# SparkFun_ESP8266_Thing.net
KiCad netlist of a schematic drawn in EAGLE
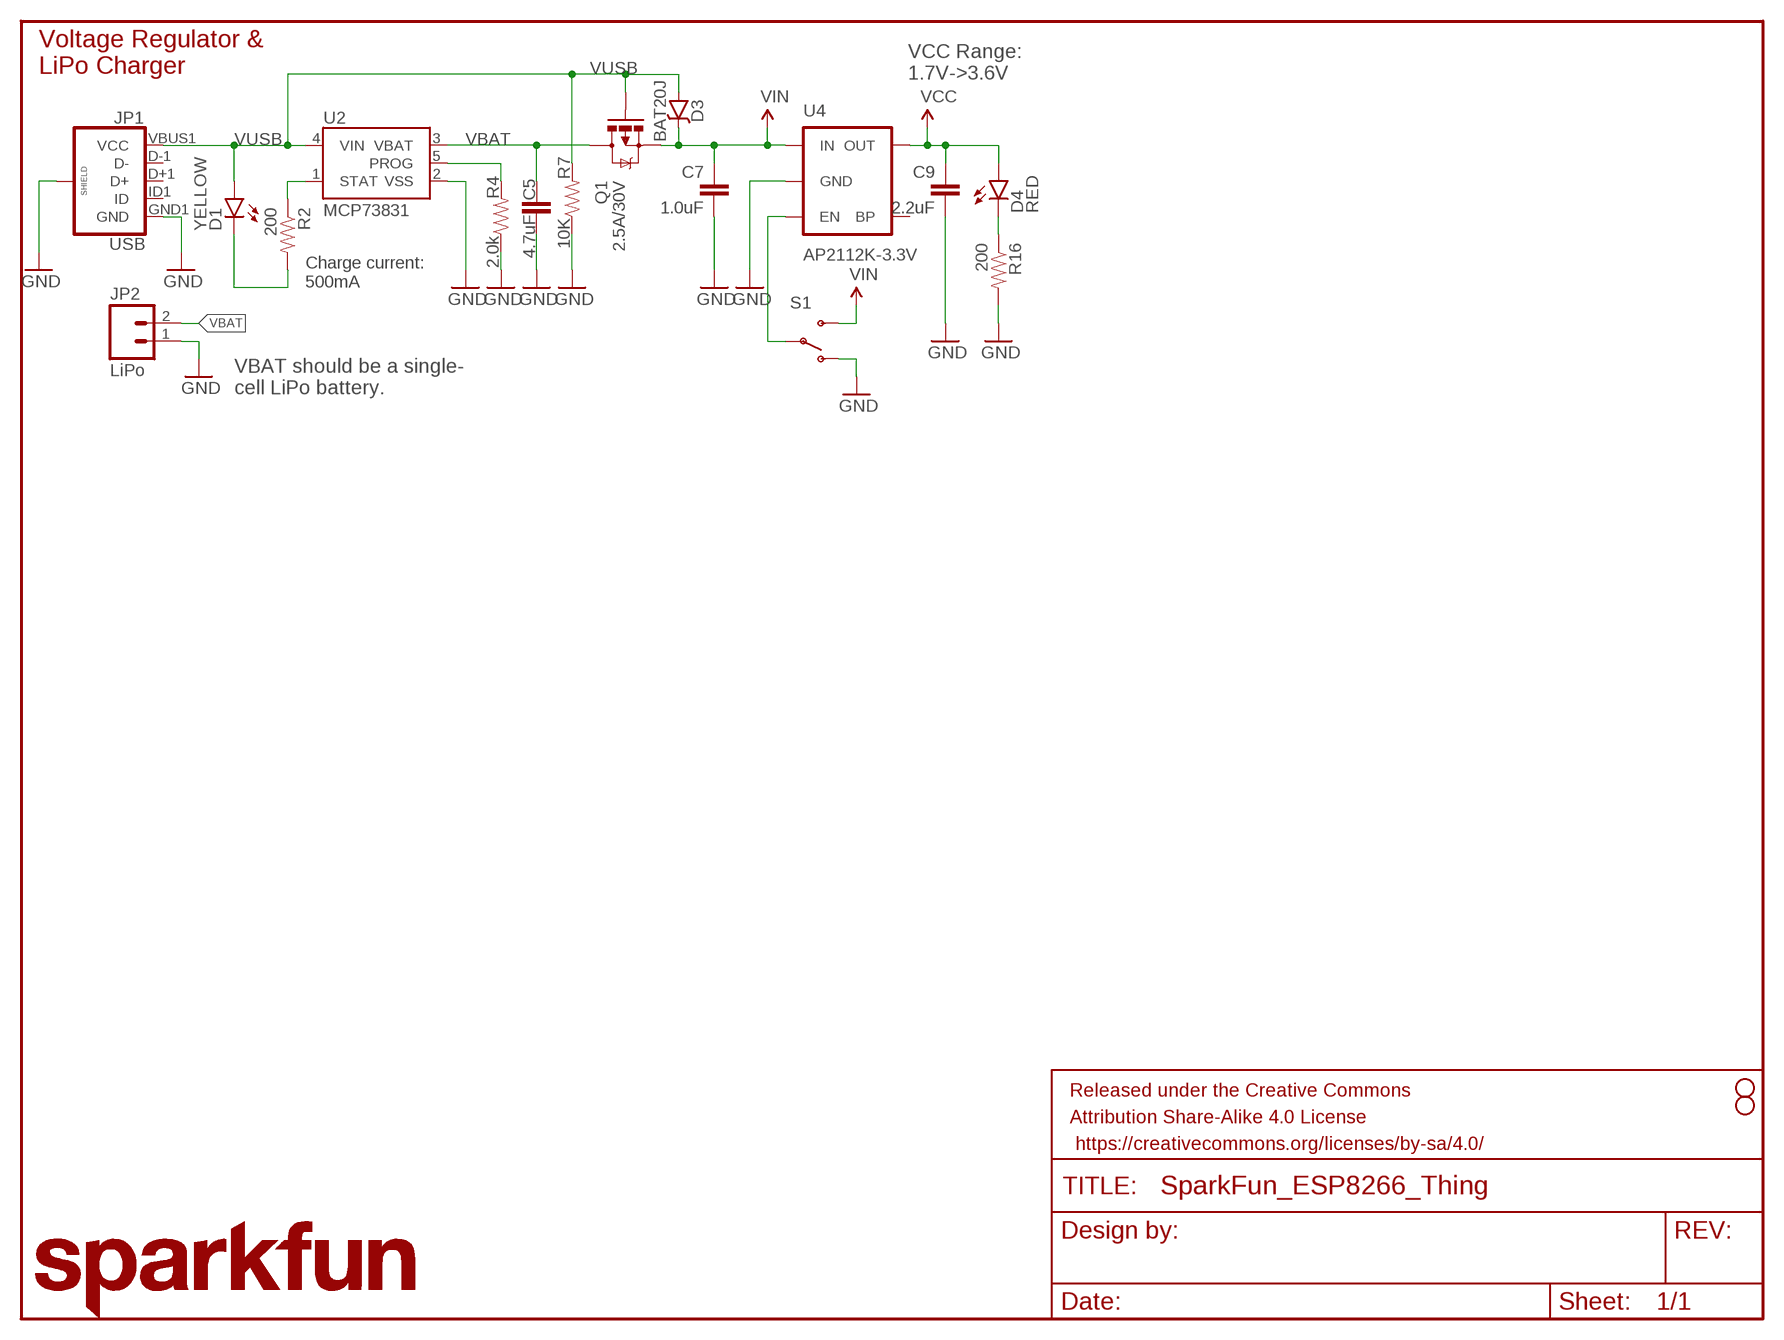
[diagram p0: schematic, sheet 1]

(export (version "E")
  (design (tool "Eeschema 10.0.6"))
  (components
    (comp (ref "C5")
      (value "4.7uF")
      (footprint "eagle-import:0603-CAP")
      (libsource (lib "eagle-import") (part "4.7UF-6.3V-10%(0603)0603"))
    )
    (comp (ref "C7")
      (value "1.0uF")
      (footprint "eagle-import:0805")
      (libsource (lib "eagle-import") (part "1.0UF-25V-+80/-20(0805)"))
    )
    (comp (ref "C9")
      (value "2.2uF")
      (footprint "eagle-import:0603-CAP")
      (libsource (lib "eagle-import") (part "2.2UF-10V-20%(0603)"))
    )
    (comp (ref "D1")
      (value "YELLOW")
      (footprint "eagle-import:LED-0603")
      (libsource (lib "eagle-import") (part "LED-YELLOW0603"))
    )
    (comp (ref "D3")
      (value "BAT20J")
      (footprint "eagle-import:SOD-323")
      (libsource (lib "eagle-import") (part "DIODE-SCHOTTKY-BAT20J"))
    )
    (comp (ref "D4")
      (value "RED")
      (footprint "eagle-import:LED-0603")
      (libsource (lib "eagle-import") (part "LED-RED0603"))
    )
    (comp (ref "FRAME1")
      (value "FRAME-LETTER")
      (footprint "eagle-import:CREATIVE_COMMONS")
      (libsource (lib "eagle-import") (part "FRAME-LETTER"))
    )
    (comp (ref "JP1")
      (value "USB")
      (footprint "eagle-import:USB-B-MICRO-SMD_V03")
      (libsource (lib "eagle-import") (part "USB_MICROB_PLUGCONN-11752"))
    )
    (comp (ref "JP2")
      (value "LiPo")
      (footprint "eagle-import:JST-2-PTH")
      (libsource (lib "eagle-import") (part "M02JST-PTH-2"))
    )
    (comp (ref "LOGO1")
      (value "SFE_LOGO_NAME.2_INCH")
      (footprint "eagle-import:SFE_LOGO_NAME_.2")
      (libsource (lib "eagle-import") (part "SFE_LOGO_NAME.2_INCH"))
    )
    (comp (ref "Q1")
      (value "2.5A/30V")
      (footprint "eagle-import:SOT23-3")
      (libsource (lib "eagle-import") (part "MOSFET-PCHANNELDMG2307L"))
    )
    (comp (ref "R2")
      (value "200")
      (footprint "eagle-import:0603-RES")
      (libsource (lib "eagle-import") (part "200OHM1/10W1%(0603)"))
    )
    (comp (ref "R4")
      (value "2.0k")
      (footprint "eagle-import:0603-RES")
      (libsource (lib "eagle-import") (part "2.0KOHM1/10W5%(0603)"))
    )
    (comp (ref "R7")
      (value "10K")
      (footprint "eagle-import:0603-RES")
      (libsource (lib "eagle-import") (part "10KOHM1/10W1%(0603)0603"))
    )
    (comp (ref "R16")
      (value "200")
      (footprint "eagle-import:0603-RES")
      (libsource (lib "eagle-import") (part "200OHM1/10W1%(0603)"))
    )
    (comp (ref "S1")
      (value "SWITCH-SPDT-SMD-A")
      (footprint "eagle-import:SWITCH-SPST-SMD-A")
      (libsource (lib "eagle-import") (part "SWITCH-SPDT-SMD-A"))
    )
    (comp (ref "STANDOFF3")
      (value "STAND-OFF")
      (footprint "eagle-import:STAND-OFF")
      (libsource (lib "eagle-import") (part "STAND-OFF"))
    )
    (comp (ref "STANDOFF4")
      (value "STAND-OFF")
      (footprint "eagle-import:STAND-OFF")
      (libsource (lib "eagle-import") (part "STAND-OFF"))
    )
    (comp (ref "U2")
      (value "MCP73831")
      (footprint "eagle-import:SOT23-5")
      (libsource (lib "eagle-import") (part "MCP73831"))
    )
    (comp (ref "U4")
      (value "AP2112K-3.3V")
      (footprint "eagle-import:SOT23-5")
      (libsource (lib "eagle-import") (part "V_REG_LDOSMD"))
    )
  )
  (nets
    (net (code "1") (name "/VUSB") (class "Default")
      (node (ref "D1") (pin "A") (pinfunction "A_A") (pintype "passive"))
      (node (ref "D3") (pin "A") (pinfunction "A_A") (pintype "passive"))
      (node (ref "JP1") (pin "VBUS1") (pinfunction "VCC_VBUS1") (pintype "bidirectional"))
      (node (ref "Q1") (pin "1") (pinfunction "G_1") (pintype "passive"))
      (node (ref "R7") (pin "2") (pinfunction "2_2") (pintype "passive"))
      (node (ref "U2") (pin "4") (pinfunction "VIN_4") (pintype "power_in"))
    )
    (net (code "2") (name "GND") (class "Default")
      (node (ref "C5") (pin "2") (pinfunction "2_2") (pintype "passive"))
      (node (ref "C7") (pin "2") (pinfunction "2_2") (pintype "passive"))
      (node (ref "C9") (pin "2") (pinfunction "2_2") (pintype "passive"))
      (node (ref "JP1") (pin "GND1") (pinfunction "GND_GND1") (pintype "bidirectional"))
      (node (ref "JP1") (pin "SHIELD1") (pinfunction "SHIELD_SHIELD1") (pintype "bidirectional"))
      (node (ref "JP1") (pin "SHIELD2") (pinfunction "SHIELD_SHIELD2") (pintype "bidirectional"))
      (node (ref "JP1") (pin "SHIELD3") (pinfunction "SHIELD_SHIELD3") (pintype "bidirectional"))
      (node (ref "JP2") (pin "1") (pinfunction "1_1") (pintype "passive"))
      (node (ref "R16") (pin "2") (pinfunction "2_2") (pintype "passive"))
      (node (ref "R4") (pin "1") (pinfunction "1_1") (pintype "passive"))
      (node (ref "R7") (pin "1") (pinfunction "1_1") (pintype "passive"))
      (node (ref "S1") (pin "1") (pinfunction "O_1") (pintype "passive"))
      (node (ref "U2") (pin "2") (pinfunction "VSS_2") (pintype "power_in"))
      (node (ref "U4") (pin "2") (pinfunction "GND_2") (pintype "input"))
    )
    (net (code "3") (name "Net-(D1-PadC)") (class "Default")
      (node (ref "D1") (pin "C") (pinfunction "C_C") (pintype "passive"))
      (node (ref "R2") (pin "2") (pinfunction "2_2") (pintype "passive"))
    )
    (net (code "4") (name "Net-(D4-PadC)") (class "Default")
      (node (ref "D4") (pin "C") (pinfunction "C_C") (pintype "passive"))
      (node (ref "R16") (pin "1") (pinfunction "1_1") (pintype "passive"))
    )
    (net (code "5") (name "Net-(S1-P)") (class "Default")
      (node (ref "S1") (pin "2") (pinfunction "P_2") (pintype "passive"))
      (node (ref "U4") (pin "3") (pinfunction "EN_3") (pintype "input"))
    )
    (net (code "6") (name "Net-(U2-PROG)") (class "Default")
      (node (ref "R4") (pin "2") (pinfunction "2_2") (pintype "passive"))
      (node (ref "U2") (pin "5") (pinfunction "PROG_5") (pintype "input"))
    )
    (net (code "7") (name "Net-(U2-STAT)") (class "Default")
      (node (ref "R2") (pin "1") (pinfunction "1_1") (pintype "passive"))
      (node (ref "U2") (pin "1") (pinfunction "STAT_1") (pintype "output"))
    )
    (net (code "8") (name "VBAT") (class "Default")
      (node (ref "C5") (pin "1") (pinfunction "1_1") (pintype "passive"))
      (node (ref "JP2") (pin "2") (pinfunction "2_2") (pintype "passive"))
      (node (ref "Q1") (pin "3") (pinfunction "D_3") (pintype "passive"))
      (node (ref "U2") (pin "3") (pinfunction "VBAT_3") (pintype "power_in"))
    )
    (net (code "9") (name "VCC") (class "Default")
      (node (ref "C9") (pin "1") (pinfunction "1_1") (pintype "passive"))
      (node (ref "D4") (pin "A") (pinfunction "A_A") (pintype "passive"))
      (node (ref "U4") (pin "5") (pinfunction "OUT_5") (pintype "passive"))
    )
    (net (code "10") (name "VIN") (class "Default")
      (node (ref "C7") (pin "1") (pinfunction "1_1") (pintype "passive"))
      (node (ref "D3") (pin "C") (pinfunction "C_C") (pintype "passive"))
      (node (ref "Q1") (pin "2") (pinfunction "S_2") (pintype "passive"))
      (node (ref "S1") (pin "3") (pinfunction "S_3") (pintype "passive"))
      (node (ref "U4") (pin "1") (pinfunction "IN_1") (pintype "input"))
    )
    (net (code "11") (name "unconnected-(JP1-D+-PadD+1)") (class "Default")
      (node (ref "JP1") (pin "D+1") (pinfunction "D+_D+1") (pintype "bidirectional"))
    )
    (net (code "12") (name "unconnected-(JP1-D--PadD-1)") (class "Default")
      (node (ref "JP1") (pin "D-1") (pinfunction "D-_D-1") (pintype "bidirectional"))
    )
    (net (code "13") (name "unconnected-(JP1-ID-PadID1)") (class "Default")
      (node (ref "JP1") (pin "ID1") (pinfunction "ID_ID1") (pintype "bidirectional"))
    )
    (net (code "14") (name "unconnected-(U4-BP-Pad4)") (class "Default")
      (node (ref "U4") (pin "4") (pinfunction "BP_4") (pintype "input"))
    )
  )
)
